# SCH_snap_2025-01-24.net
KiCad netlist of a schematic drawn in EasyEDA
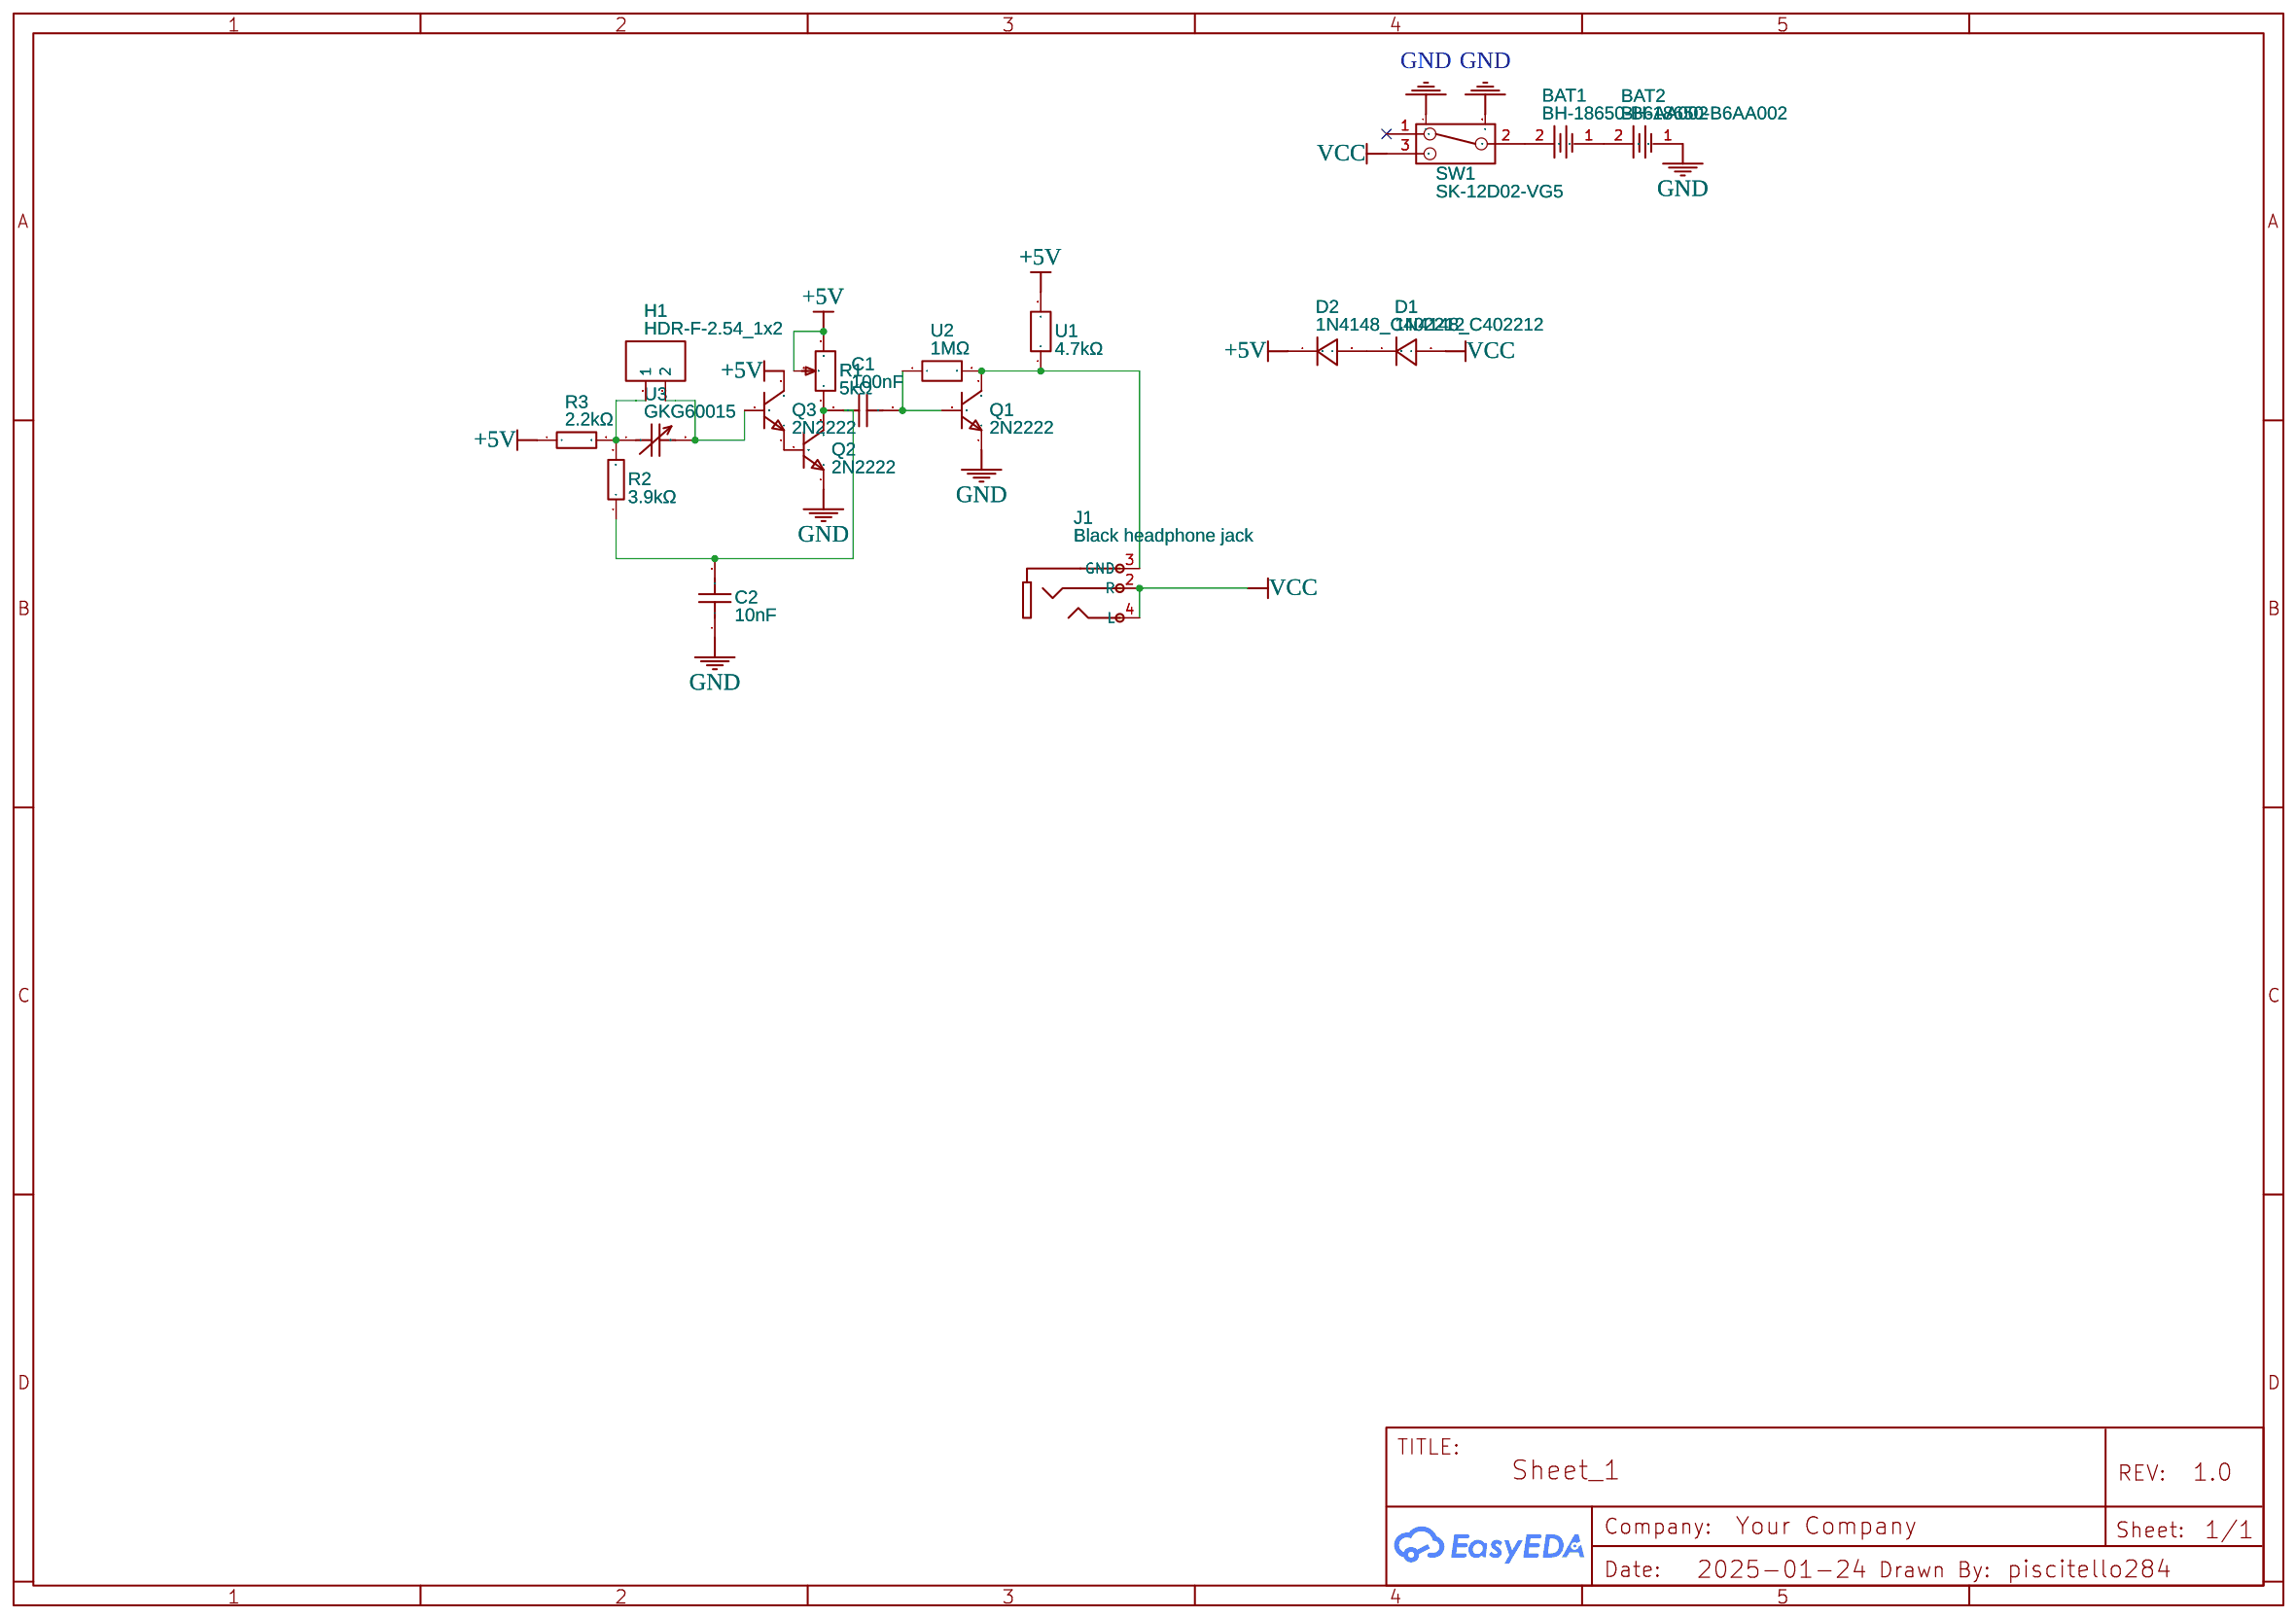
[diagram p0: schematic sheet]

(export (version "E")
  (design (tool "Eeschema 10.0.6"))
  (components
    (comp (ref "BAT1")
      (value "BH-18650-B6AA002")
      (fields (field (name "Manufacturer") "MYOUNG(美阳)"))
      (libsource (lib "") (part "BH-18650-B6AA002"))
    )
    (comp (ref "BAT2")
      (value "BH-18650-B6AA002")
      (fields (field (name "Manufacturer") "MYOUNG(美阳)"))
      (libsource (lib "") (part "BH-18650-B6AA002"))
    )
    (comp (ref "C1")
      (value "100nF")
      (fields (field (name "Manufacturer Part") "PX104K2W1502") (field (name "Manufacturer") "KYET(科雅)"))
      (libsource (lib "") (part "PX104K2W1502"))
    )
    (comp (ref "C2")
      (value "10nF")
      (fields (field (name "Manufacturer Part") "A103K15X7RF5TAA") (field (name "Manufacturer") "VISHAY(威世)"))
      (libsource (lib "") (part "A103K15X7RF5TAA"))
    )
    (comp (ref "D1")
      (value "1N4148_C402212")
      (fields (field (name "Manufacturer Part") "1N4148") (field (name "Manufacturer") "LGE(鲁光)"))
      (libsource (lib "") (part "1N4148_C402212"))
    )
    (comp (ref "D2")
      (value "1N4148_C402212")
      (fields (field (name "Manufacturer Part") "1N4148") (field (name "Manufacturer") "LGE(鲁光)"))
      (libsource (lib "") (part "1N4148_C402212"))
    )
    (comp (ref "H1") (value "HDR-F-2.54_1x2") (libsource (lib "") (part "HDR-F-2.54_1x2")))
    (comp (ref "J1")
      (value "Black headphone jack")
      (fields (field (name "Manufacturer Part") "320B直插") (field (name "Manufacturer") "BOOMELE(博穆精密)"))
      (libsource (lib "") (part "Black headphone jack"))
    )
    (comp (ref "Q1")
      (value "2N2222")
      (fields (field (name "Manufacturer Part") "2N2222A") (field (name "Manufacturer") "ST(先科)"))
      (libsource (lib "") (part "2N2222"))
    )
    (comp (ref "Q2")
      (value "2N2222")
      (fields (field (name "Manufacturer Part") "2N2222A") (field (name "Manufacturer") "ST(先科)"))
      (libsource (lib "") (part "2N2222"))
    )
    (comp (ref "Q3")
      (value "2N2222")
      (fields (field (name "Manufacturer Part") "2N2222A") (field (name "Manufacturer") "ST(先科)"))
      (libsource (lib "") (part "2N2222"))
    )
    (comp (ref "R1")
      (value "5kΩ")
      (fields (field (name "Manufacturer Part") "3386P-1-502") (field (name "Manufacturer") "BOCHEN(博晨)"))
      (libsource (lib "") (part "3386P-1-502_C330582"))
    )
    (comp (ref "R2")
      (value "3.9kΩ")
      (fields (field (name "Manufacturer Part") "RC0603FR-073K9L") (field (name "Manufacturer") "YAGEO(国巨)"))
      (libsource (lib "") (part "RC0603FR-073K9L"))
    )
    (comp (ref "R3")
      (value "2.2kΩ")
      (fields (field (name "Manufacturer Part") "PTFR0805B2K20N9") (field (name "Manufacturer") "RESI(开步睿思)"))
      (libsource (lib "") (part "PTFR0805B2K20N9"))
    )
    (comp (ref "SW1")
      (value "SK-12D02-VG5")
      (fields (field (name "Manufacturer") "Rectangular Connectors - Contacts"))
      (libsource (lib "") (part "SK-12D02-VG5"))
    )
    (comp (ref "U1")
      (value "4.7kΩ")
      (fields (field (name "Manufacturer Part") "SCR2512J4K7") (field (name "Manufacturer") "VO(翔胜)"))
      (libsource (lib "") (part "SCR2512J4K7"))
    )
    (comp (ref "U2")
      (value "1MΩ")
      (fields (field (name "Manufacturer Part") "SCR0603F1M") (field (name "Manufacturer") "VO(翔胜)"))
      (libsource (lib "") (part "SCR0603F1M"))
    )
    (comp (ref "U3")
      (value "GKG60015")
      (fields (field (name "Manufacturer") "EW Electronics"))
      (libsource (lib "") (part "GKG60015"))
    )
  )
  (nets
    (net (code "1") (name "+5V") (class "Default")
      (node (ref "D2") (pin "1") (pinfunction "C_1") (pintype "unspecified"))
      (node (ref "Q3") (pin "3") (pinfunction "C_3") (pintype "unspecified"))
      (node (ref "R1") (pin "2") (pinfunction "2_2") (pintype "input"))
      (node (ref "R1") (pin "3") (pinfunction "3_3") (pintype "input"))
      (node (ref "R3") (pin "1") (pinfunction "1_1") (pintype "unspecified"))
      (node (ref "U1") (pin "2") (pinfunction "2_2") (pintype "unspecified"))
    )
    (net (code "2") (name "GND") (class "Default")
      (node (ref "BAT2") (pin "1") (pinfunction "1_1") (pintype "input"))
      (node (ref "C2") (pin "1") (pinfunction "1_1") (pintype "unspecified"))
      (node (ref "Q1") (pin "1") (pinfunction "E_1") (pintype "unspecified"))
      (node (ref "Q2") (pin "1") (pinfunction "E_1") (pintype "unspecified"))
      (node (ref "SW1") (pin "4") (pinfunction "4_4") (pintype "unspecified"))
      (node (ref "SW1") (pin "5") (pinfunction "5_5") (pintype "unspecified"))
    )
    (net (code "3") (name "Net-(BAT1-Pad1)") (class "Default")
      (node (ref "BAT1") (pin "1") (pinfunction "1_1") (pintype "input"))
      (node (ref "BAT2") (pin "2") (pinfunction "2_2") (pintype "input"))
    )
    (net (code "4") (name "Net-(BAT1-Pad2)") (class "Default")
      (node (ref "BAT1") (pin "2") (pinfunction "2_2") (pintype "input"))
      (node (ref "SW1") (pin "2") (pinfunction "2_2") (pintype "unspecified"))
    )
    (net (code "5") (name "Net-(D1-C)") (class "Default")
      (node (ref "D1") (pin "1") (pinfunction "C_1") (pintype "unspecified"))
      (node (ref "D2") (pin "2") (pinfunction "A_2") (pintype "unspecified"))
    )
    (net (code "6") (name "Net-(H1-Pad1)") (class "Default")
      (node (ref "H1") (pin "1") (pinfunction "1_1") (pintype "input"))
      (node (ref "R2") (pin "2") (pinfunction "2_2") (pintype "input"))
      (node (ref "R3") (pin "2") (pinfunction "2_2") (pintype "unspecified"))
      (node (ref "U3") (pin "1") (pinfunction "1_1") (pintype "unspecified"))
    )
    (net (code "7") (name "Net-(J1-GND)") (class "Default")
      (node (ref "J1") (pin "3") (pinfunction "GND_3") (pintype "input"))
      (node (ref "Q1") (pin "3") (pinfunction "C_3") (pintype "unspecified"))
      (node (ref "U1") (pin "1") (pinfunction "1_1") (pintype "unspecified"))
      (node (ref "U2") (pin "2") (pinfunction "2_2") (pintype "unspecified"))
    )
    (net (code "8") (name "Net-(Q1-B)") (class "Default")
      (node (ref "C1") (pin "2") (pinfunction "2_2") (pintype "unspecified"))
      (node (ref "Q1") (pin "2") (pinfunction "B_2") (pintype "unspecified"))
      (node (ref "U2") (pin "1") (pinfunction "1_1") (pintype "unspecified"))
    )
    (net (code "9") (name "Net-(Q2-B)") (class "Default")
      (node (ref "Q2") (pin "2") (pinfunction "B_2") (pintype "unspecified"))
      (node (ref "Q3") (pin "1") (pinfunction "E_1") (pintype "unspecified"))
    )
    (net (code "10") (name "Net-(Q2-C)") (class "Default")
      (node (ref "C1") (pin "1") (pinfunction "1_1") (pintype "unspecified"))
      (node (ref "C2") (pin "2") (pinfunction "2_2") (pintype "unspecified"))
      (node (ref "Q2") (pin "3") (pinfunction "C_3") (pintype "unspecified"))
      (node (ref "R1") (pin "1") (pinfunction "1_1") (pintype "input"))
      (node (ref "R2") (pin "1") (pinfunction "1_1") (pintype "input"))
    )
    (net (code "11") (name "Net-(Q3-B)") (class "Default")
      (node (ref "H1") (pin "2") (pinfunction "2_2") (pintype "input"))
      (node (ref "Q3") (pin "2") (pinfunction "B_2") (pintype "unspecified"))
      (node (ref "U3") (pin "2") (pinfunction "2_2") (pintype "unspecified"))
    )
    (net (code "12") (name "VCC") (class "Default")
      (node (ref "D1") (pin "2") (pinfunction "A_2") (pintype "unspecified"))
      (node (ref "J1") (pin "2") (pinfunction "R_2") (pintype "input"))
      (node (ref "J1") (pin "4") (pinfunction "L_4") (pintype "input"))
      (node (ref "SW1") (pin "3") (pinfunction "3_3") (pintype "unspecified"))
    )
    (net (code "13") (name "unconnected-(SW1-Pad1)") (class "Default")
      (node (ref "SW1") (pin "1") (pinfunction "1_1") (pintype "unspecified+no_connect"))
    )
  )
)
